# SCH_HomeAuto_2022-10-05.net
KiCad netlist of a schematic drawn in EasyEDA
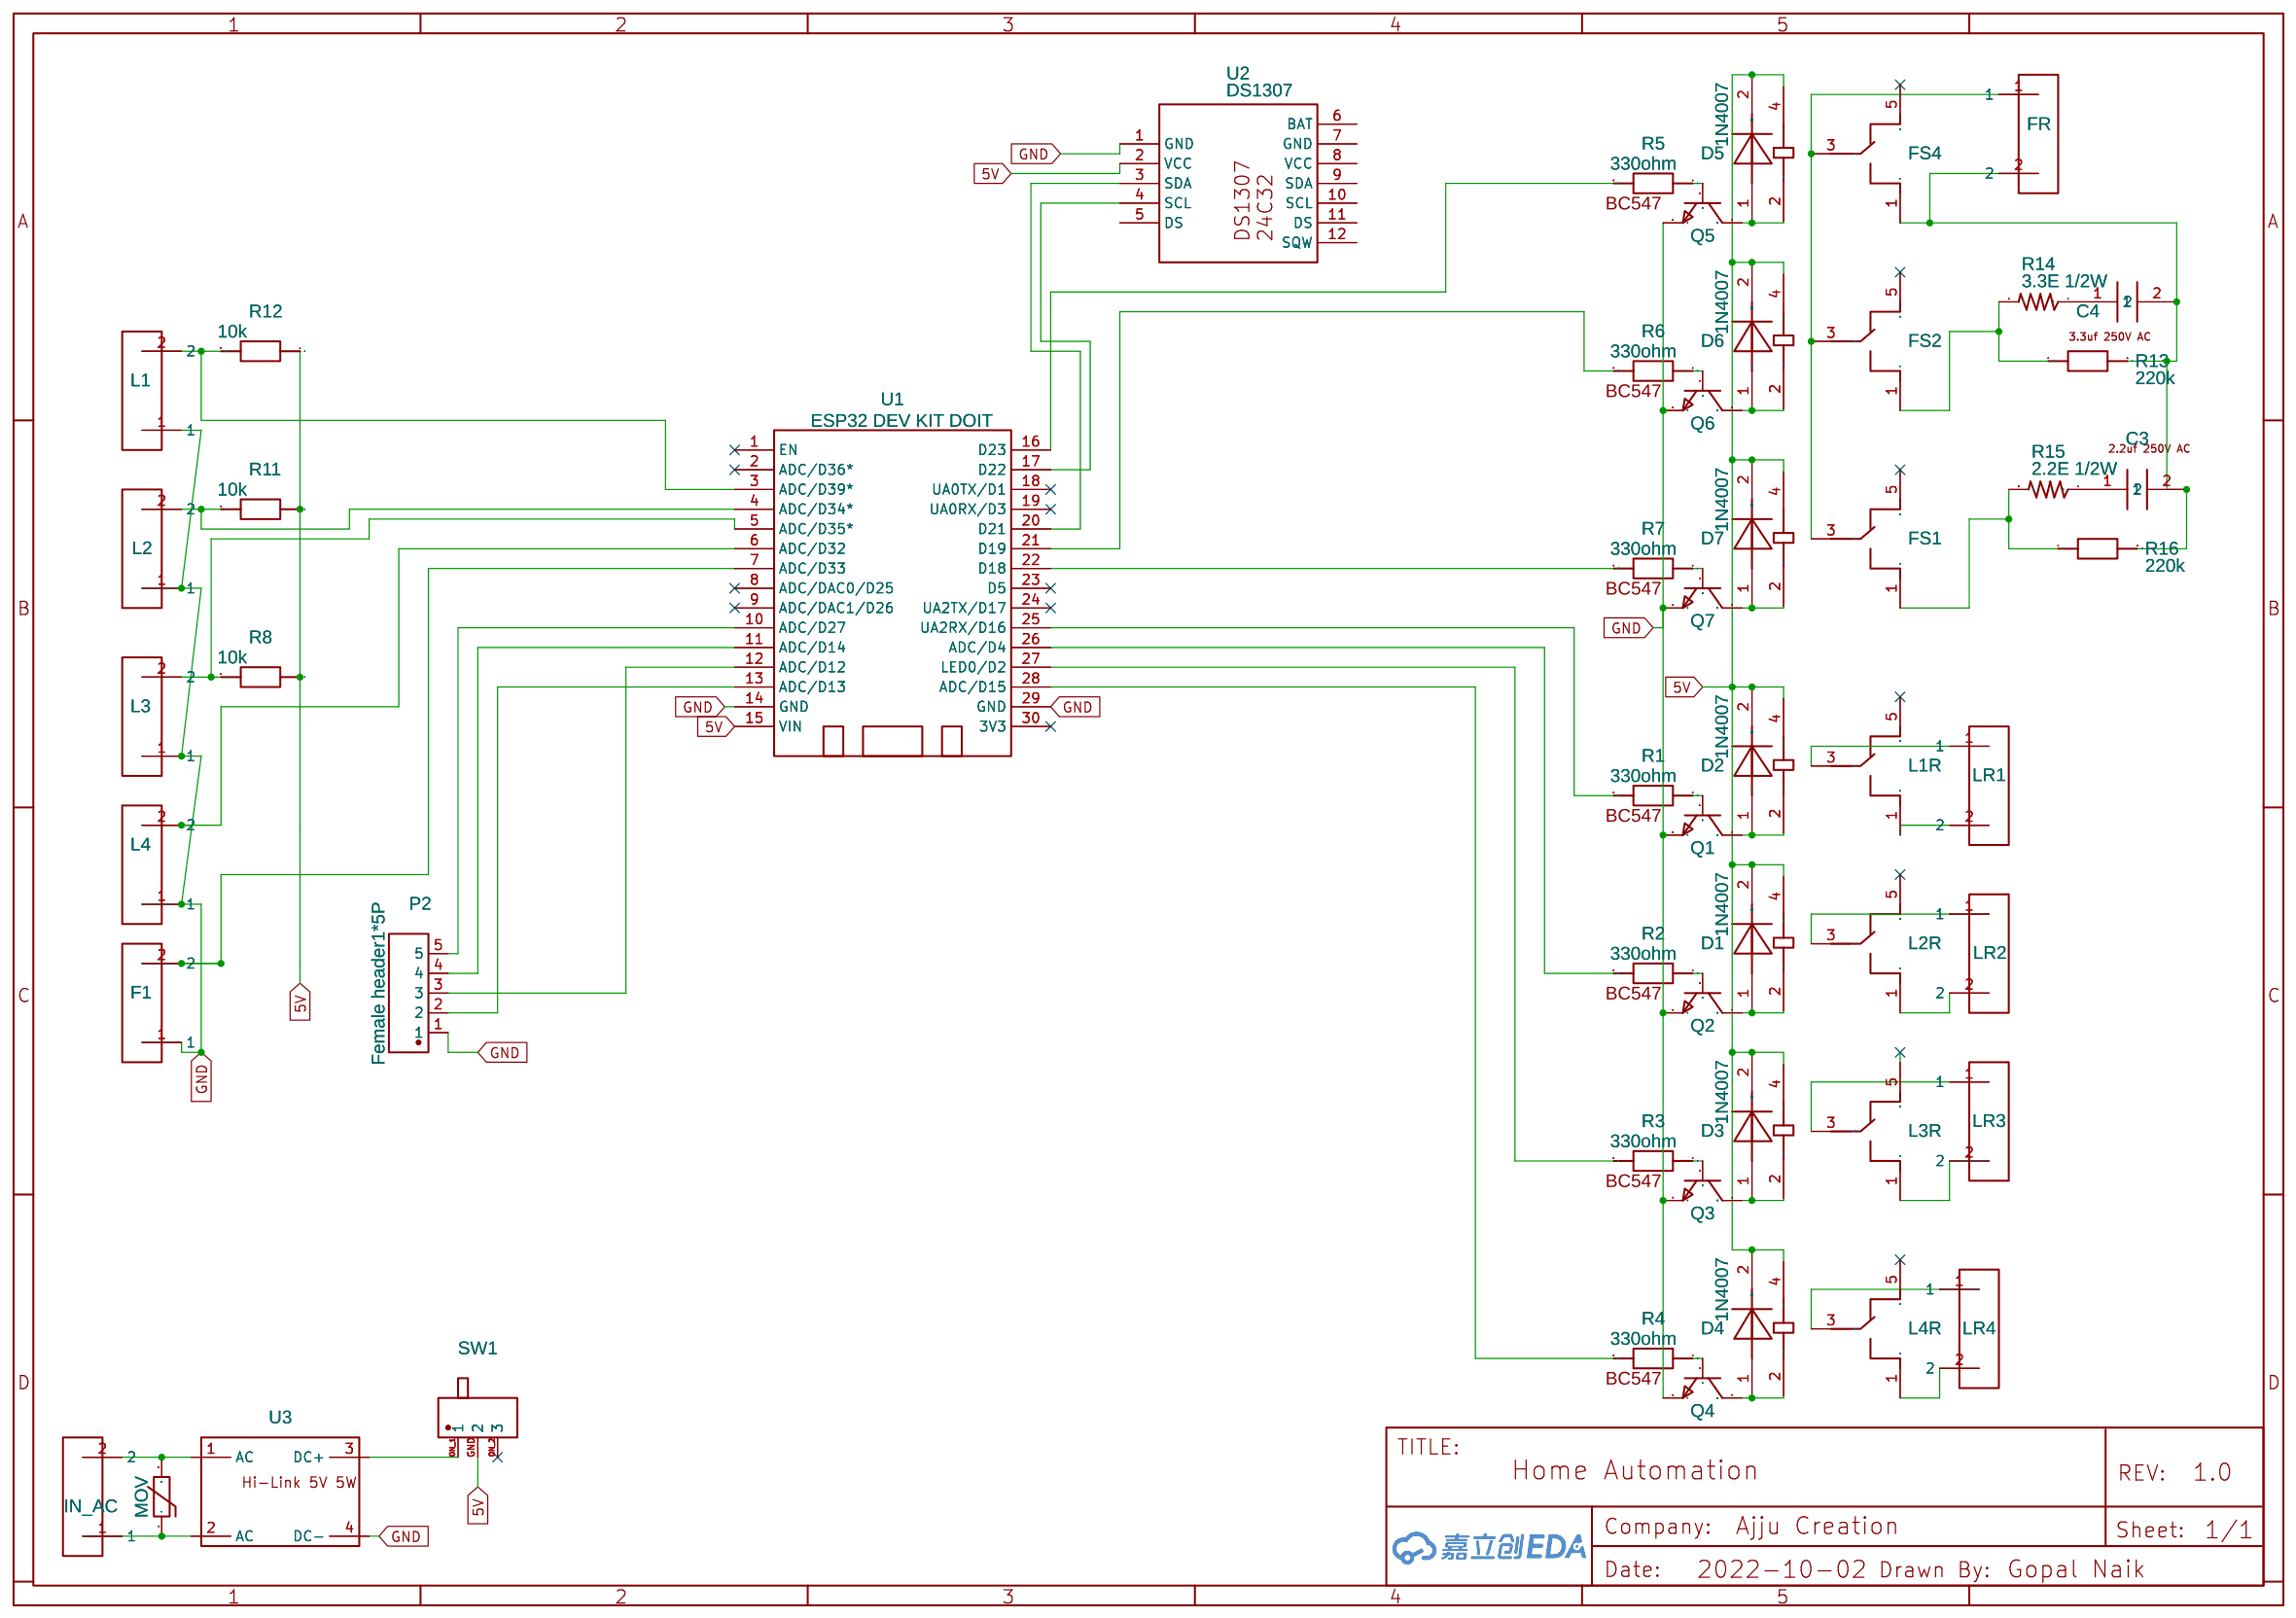
[diagram p0: schematic sheet]

(export (version "E")
  (design (tool "Eeschema 10.0.6"))
  (components
    (comp (ref "C3")
      (value "New_Symbol 2.2 uf 250v ac")
      (libsource (lib "") (part "New_Symbol 2.2 uf 250v ac"))
    )
    (comp (ref "C4")
      (value "New_Symbol 2.2 uf 250v ac")
      (libsource (lib "") (part "New_Symbol 2.2 uf 250v ac_1"))
    )
    (comp (ref "D1")
      (value "1N4007")
      (fields (field (name "BOM_Manufacturer Part") "DIODE") (field (name "BOM_Supplier Part") "undefined"))
      (libsource (lib "") (part "1N4007"))
    )
    (comp (ref "D2")
      (value "1N4007")
      (fields (field (name "BOM_Manufacturer Part") "DIODE") (field (name "BOM_Supplier Part") "undefined"))
      (libsource (lib "") (part "1N4007"))
    )
    (comp (ref "D3")
      (value "1N4007")
      (fields (field (name "BOM_Manufacturer Part") "DIODE") (field (name "BOM_Supplier Part") "undefined"))
      (libsource (lib "") (part "1N4007"))
    )
    (comp (ref "D4")
      (value "1N4007")
      (fields (field (name "BOM_Manufacturer Part") "DIODE") (field (name "BOM_Supplier Part") "undefined"))
      (libsource (lib "") (part "1N4007"))
    )
    (comp (ref "D5")
      (value "1N4007")
      (fields (field (name "BOM_Manufacturer Part") "DIODE") (field (name "BOM_Supplier Part") "undefined"))
      (libsource (lib "") (part "1N4007"))
    )
    (comp (ref "D6")
      (value "1N4007")
      (fields (field (name "BOM_Manufacturer Part") "DIODE") (field (name "BOM_Supplier Part") "undefined"))
      (libsource (lib "") (part "1N4007"))
    )
    (comp (ref "D7")
      (value "1N4007")
      (fields (field (name "BOM_Manufacturer Part") "DIODE") (field (name "BOM_Supplier Part") "undefined"))
      (libsource (lib "") (part "1N4007"))
    )
    (comp (ref "F1")
      (value "2 Pin Plug-In Screw Terminal Block 5.08mm pitch")
      (libsource (lib "") (part "2 Pin Plug-In Screw Terminal Block 5.08mm pitch_4"))
    )
    (comp (ref "FR")
      (value "2 Pin Plug-In Screw Terminal Block 5.08mm pitch")
      (libsource (lib "") (part "2 Pin Plug-In Screw Terminal Block 5.08mm pitch"))
    )
    (comp (ref "FS1")
      (value "RELAY-SPST")
      (fields
        (field (name "BOM_Manufacturer Part") "Relay-SPST")
        (field (name "BOM_Supplier Part") "C2941249")
      )
      (libsource (lib "") (part "RELAY-SPST"))
    )
    (comp (ref "FS2")
      (value "RELAY-SPST")
      (fields
        (field (name "BOM_Manufacturer Part") "Relay-SPST")
        (field (name "BOM_Supplier Part") "C2941249")
      )
      (libsource (lib "") (part "RELAY-SPST"))
    )
    (comp (ref "FS4")
      (value "RELAY-SPST")
      (fields
        (field (name "BOM_Manufacturer Part") "Relay-SPST")
        (field (name "BOM_Supplier Part") "C2941249")
      )
      (libsource (lib "") (part "RELAY-SPST"))
    )
    (comp (ref "IN_AC")
      (value "2 Pin Plug-In Screw Terminal Block 5.08mm pitch")
      (libsource (lib "") (part "2 Pin Plug-In Screw Terminal Block 5.08mm pitch_3"))
    )
    (comp (ref "L1")
      (value "2 Pin Plug-In Screw Terminal Block 5.08mm pitch")
      (libsource (lib "") (part "2 Pin Plug-In Screw Terminal Block 5.08mm pitch_1"))
    )
    (comp (ref "L1R")
      (value "RELAY-SPST")
      (fields
        (field (name "BOM_Manufacturer Part") "Relay-SPST")
        (field (name "BOM_Supplier Part") "C2941249")
      )
      (libsource (lib "") (part "RELAY-SPST_3"))
    )
    (comp (ref "L2")
      (value "2 Pin Plug-In Screw Terminal Block 5.08mm pitch")
      (libsource (lib "") (part "2 Pin Plug-In Screw Terminal Block 5.08mm pitch_1"))
    )
    (comp (ref "L2R")
      (value "RELAY-SPST")
      (fields
        (field (name "BOM_Manufacturer Part") "Relay-SPST")
        (field (name "BOM_Supplier Part") "C2941249")
      )
      (libsource (lib "") (part "RELAY-SPST_4"))
    )
    (comp (ref "L3")
      (value "2 Pin Plug-In Screw Terminal Block 5.08mm pitch")
      (libsource (lib "") (part "2 Pin Plug-In Screw Terminal Block 5.08mm pitch_1"))
    )
    (comp (ref "L3R")
      (value "RELAY-SPST")
      (fields
        (field (name "BOM_Manufacturer Part") "Relay-SPST")
        (field (name "BOM_Supplier Part") "C2941249")
      )
      (libsource (lib "") (part "RELAY-SPST_1"))
    )
    (comp (ref "L4")
      (value "2 Pin Plug-In Screw Terminal Block 5.08mm pitch")
      (libsource (lib "") (part "2 Pin Plug-In Screw Terminal Block 5.08mm pitch_1"))
    )
    (comp (ref "L4R")
      (value "RELAY-SPST")
      (fields
        (field (name "BOM_Manufacturer Part") "Relay-SPST")
        (field (name "BOM_Supplier Part") "C2941249")
      )
      (libsource (lib "") (part "RELAY-SPST_2"))
    )
    (comp (ref "LR1")
      (value "2 Pin Plug-In Screw Terminal Block 5.08mm pitch")
      (libsource (lib "") (part "2 Pin Plug-In Screw Terminal Block 5.08mm pitch_2"))
    )
    (comp (ref "LR2")
      (value "2 Pin Plug-In Screw Terminal Block 5.08mm pitch")
      (libsource (lib "") (part "2 Pin Plug-In Screw Terminal Block 5.08mm pitch_2"))
    )
    (comp (ref "LR3")
      (value "2 Pin Plug-In Screw Terminal Block 5.08mm pitch")
      (libsource (lib "") (part "2 Pin Plug-In Screw Terminal Block 5.08mm pitch_2"))
    )
    (comp (ref "LR4")
      (value "2 Pin Plug-In Screw Terminal Block 5.08mm pitch")
      (libsource (lib "") (part "2 Pin Plug-In Screw Terminal Block 5.08mm pitch_2"))
    )
    (comp (ref "P2")
      (value "Female header1*5P")
      (fields (field (name "BOM_Supplier Part") "C66508"))
      (libsource (lib "") (part "Female header1*5P"))
    )
    (comp (ref "Q1") (value "BC547") (libsource (lib "") (part "BC547")))
    (comp (ref "Q2") (value "BC547") (libsource (lib "") (part "BC547")))
    (comp (ref "Q3") (value "BC547") (libsource (lib "") (part "BC547")))
    (comp (ref "Q4") (value "BC547") (libsource (lib "") (part "BC547")))
    (comp (ref "Q5") (value "BC547") (libsource (lib "") (part "BC547")))
    (comp (ref "Q6") (value "BC547") (libsource (lib "") (part "BC547")))
    (comp (ref "Q7") (value "BC547") (libsource (lib "") (part "BC547")))
    (comp (ref "R1") (value "330ohm") (libsource (lib "") (part "330 OHM 0.25W 11MM")))
    (comp (ref "R2") (value "330ohm") (libsource (lib "") (part "330 OHM 0.25W 11MM")))
    (comp (ref "R3") (value "330ohm") (libsource (lib "") (part "330 OHM 0.25W 11MM")))
    (comp (ref "R4") (value "330ohm") (libsource (lib "") (part "330 OHM 0.25W 11MM")))
    (comp (ref "R5") (value "330ohm") (libsource (lib "") (part "330 OHM 0.25W 11MM")))
    (comp (ref "R6") (value "330ohm") (libsource (lib "") (part "330 OHM 0.25W 11MM")))
    (comp (ref "R7") (value "330ohm") (libsource (lib "") (part "330 OHM 0.25W 11MM")))
    (comp (ref "R8") (value "10k") (libsource (lib "") (part "330 OHM 0.25W 11MM")))
    (comp (ref "R11") (value "10k") (libsource (lib "") (part "330 OHM 0.25W 11MM")))
    (comp (ref "R12") (value "10k") (libsource (lib "") (part "330 OHM 0.25W 11MM")))
    (comp (ref "R13") (value "220k") (libsource (lib "") (part "330 OHM 0.25W 11MM_1")))
    (comp (ref "R14") (value "3.3E 1/2W") (libsource (lib "") (part "2.2E RESISTANCE 1/2W")))
    (comp (ref "R15") (value "2.2E 1/2W") (libsource (lib "") (part "2.2E RESISTANCE 1/2W")))
    (comp (ref "R16") (value "220k") (libsource (lib "") (part "330 OHM 0.25W 11MM_1")))
    (comp (ref "SW1")
      (value "3-Pin SPDT Slide Switch")
      (fields
        (field (name "BOM_Manufacturer Part") "5MS1S102BM1QES")
        (field (name "BOM_Supplier Part") "C496203")
      )
      (libsource (lib "") (part "3-Pin SPDT Slide Switch"))
    )
    (comp (ref "U1") (value "ESP32 DEV KIT DOIT") (libsource (lib "") (part "ESP32 DEV KIT DOIT")))
    (comp (ref "U2")
      (value "DS1307")
      (fields (field (name "BOM_Supplier Part") "undefined"))
      (libsource (lib "") (part "DS1307"))
    )
    (comp (ref "U3")
      (value "HLK-5M05 Hi-Link 5V 5W")
      (fields
        (field (name "BOM_Manufacturer Part") "HLK-5M05")
        (field (name "BOM_Supplier Part") "Hi-Link AC-DC Module 5V 1A - 5W")
      )
      (libsource (lib "") (part "HLK-5M05 Hi-Link 5V 5W"))
    )
    (comp (ref "VAR1")
      (value "MOV")
      (fields
        (field (name "BOM_Manufacturer Part") "MOV-14D781K")
        (field (name "BOM_Supplier Part") "652-MOV-14D781K")
      )
      (libsource (lib "") (part "VAR - MOV-14D781K"))
    )
  )
  (nets
    (net (code "1") (name "5V") (class "Default")
      (node (ref "D1") (pin "2") (pinfunction "Diode_IN4007_2") (pintype "unspecified"))
      (node (ref "D2") (pin "2") (pinfunction "Diode_IN4007_2") (pintype "unspecified"))
      (node (ref "D3") (pin "2") (pinfunction "Diode_IN4007_2") (pintype "unspecified"))
      (node (ref "D4") (pin "2") (pinfunction "Diode_IN4007_2") (pintype "unspecified"))
      (node (ref "D5") (pin "2") (pinfunction "Diode_IN4007_2") (pintype "unspecified"))
      (node (ref "D6") (pin "2") (pinfunction "Diode_IN4007_2") (pintype "unspecified"))
      (node (ref "D7") (pin "2") (pinfunction "Diode_IN4007_2") (pintype "unspecified"))
      (node (ref "FS1") (pin "4") (pinfunction "4_4") (pintype "unspecified"))
      (node (ref "FS2") (pin "4") (pinfunction "4_4") (pintype "unspecified"))
      (node (ref "FS4") (pin "4") (pinfunction "4_4") (pintype "unspecified"))
      (node (ref "L1R") (pin "4") (pinfunction "4_4") (pintype "unspecified"))
      (node (ref "L2R") (pin "4") (pinfunction "4_4") (pintype "unspecified"))
      (node (ref "L3R") (pin "4") (pinfunction "4_4") (pintype "unspecified"))
      (node (ref "L4R") (pin "4") (pinfunction "4_4") (pintype "unspecified"))
      (node (ref "R11") (pin "1") (pinfunction "1_1") (pintype "unspecified"))
      (node (ref "R12") (pin "1") (pinfunction "1_1") (pintype "unspecified"))
      (node (ref "R8") (pin "1") (pinfunction "1_1") (pintype "unspecified"))
      (node (ref "SW1") (pin "GND") (pinfunction "2_GND") (pintype "unspecified"))
      (node (ref "U1") (pin "15") (pinfunction "VIN_15") (pintype "input"))
      (node (ref "U2") (pin "2") (pinfunction "VCC_2") (pintype "unspecified"))
    )
    (net (code "2") (name "GND") (class "Default")
      (node (ref "F1") (pin "1") (pinfunction "1_1") (pintype "unspecified"))
      (node (ref "L1") (pin "1") (pinfunction "1_1") (pintype "unspecified"))
      (node (ref "L2") (pin "1") (pinfunction "1_1") (pintype "unspecified"))
      (node (ref "L3") (pin "1") (pinfunction "1_1") (pintype "unspecified"))
      (node (ref "L4") (pin "1") (pinfunction "1_1") (pintype "unspecified"))
      (node (ref "P2") (pin "1") (pinfunction "1_1") (pintype "unspecified"))
      (node (ref "Q1") (pin "3") (pinfunction "E_3") (pintype "unspecified"))
      (node (ref "Q2") (pin "3") (pinfunction "E_3") (pintype "unspecified"))
      (node (ref "Q3") (pin "3") (pinfunction "E_3") (pintype "unspecified"))
      (node (ref "Q4") (pin "3") (pinfunction "E_3") (pintype "unspecified"))
      (node (ref "Q5") (pin "3") (pinfunction "E_3") (pintype "unspecified"))
      (node (ref "Q6") (pin "3") (pinfunction "E_3") (pintype "unspecified"))
      (node (ref "Q7") (pin "3") (pinfunction "E_3") (pintype "unspecified"))
      (node (ref "U1") (pin "14") (pinfunction "GND_14") (pintype "bidirectional"))
      (node (ref "U1") (pin "29") (pinfunction "GND_29") (pintype "bidirectional"))
      (node (ref "U2") (pin "1") (pinfunction "GND_1") (pintype "unspecified"))
      (node (ref "U3") (pin "4") (pinfunction "DC-_4") (pintype "unspecified"))
    )
    (net (code "3") (name "Net-(C3-Pad1)") (class "Default")
      (node (ref "C3") (pin "1") (pinfunction "1_1") (pintype "unspecified"))
      (node (ref "R15") (pin "1") (pinfunction "1_1") (pintype "unspecified"))
    )
    (net (code "4") (name "Net-(C3-Pad2)") (class "Default")
      (node (ref "C3") (pin "2") (pinfunction "2_2") (pintype "unspecified"))
      (node (ref "C4") (pin "2") (pinfunction "2_2") (pintype "unspecified"))
      (node (ref "FR") (pin "2") (pinfunction "2_2") (pintype "unspecified"))
      (node (ref "FS4") (pin "1") (pinfunction "1_1") (pintype "unspecified"))
      (node (ref "R13") (pin "2") (pinfunction "2_2") (pintype "unspecified"))
      (node (ref "R16") (pin "2") (pinfunction "2_2") (pintype "unspecified"))
    )
    (net (code "5") (name "Net-(C4-Pad1)") (class "Default")
      (node (ref "C4") (pin "1") (pinfunction "1_1") (pintype "unspecified"))
      (node (ref "R14") (pin "1") (pinfunction "1_1") (pintype "unspecified"))
    )
    (net (code "6") (name "Net-(FR-Pad1)") (class "Default")
      (node (ref "FR") (pin "1") (pinfunction "1_1") (pintype "unspecified"))
      (node (ref "FS1") (pin "3") (pinfunction "3_3") (pintype "unspecified"))
      (node (ref "FS2") (pin "3") (pinfunction "3_3") (pintype "unspecified"))
      (node (ref "FS4") (pin "3") (pinfunction "3_3") (pintype "unspecified"))
    )
    (net (code "7") (name "Net-(FS1-Pad1)") (class "Default")
      (node (ref "FS1") (pin "1") (pinfunction "1_1") (pintype "unspecified"))
      (node (ref "R15") (pin "2") (pinfunction "2_2") (pintype "unspecified"))
      (node (ref "R16") (pin "1") (pinfunction "1_1") (pintype "unspecified"))
    )
    (net (code "8") (name "Net-(FS2-Pad1)") (class "Default")
      (node (ref "FS2") (pin "1") (pinfunction "1_1") (pintype "unspecified"))
      (node (ref "R13") (pin "1") (pinfunction "1_1") (pintype "unspecified"))
      (node (ref "R14") (pin "2") (pinfunction "2_2") (pintype "unspecified"))
    )
    (net (code "9") (name "Net-(IN_AC-Pad1)") (class "Default")
      (node (ref "IN_AC") (pin "1") (pinfunction "1_1") (pintype "unspecified"))
      (node (ref "U3") (pin "2") (pinfunction "AC_2") (pintype "unspecified"))
      (node (ref "VAR1") (pin "1") (pinfunction "1_1") (pintype "unspecified"))
    )
    (net (code "10") (name "Net-(IN_AC-Pad2)") (class "Default")
      (node (ref "IN_AC") (pin "2") (pinfunction "2_2") (pintype "unspecified"))
      (node (ref "U3") (pin "1") (pinfunction "AC_1") (pintype "unspecified"))
      (node (ref "VAR1") (pin "2") (pinfunction "2_2") (pintype "unspecified"))
    )
    (net (code "11") (name "Net-(L1R-Pad1)") (class "Default")
      (node (ref "L1R") (pin "1") (pinfunction "1_1") (pintype "unspecified"))
      (node (ref "LR1") (pin "2") (pinfunction "2_2") (pintype "unspecified"))
    )
    (net (code "12") (name "Net-(L1R-Pad3)") (class "Default")
      (node (ref "L1R") (pin "3") (pinfunction "3_3") (pintype "unspecified"))
      (node (ref "LR1") (pin "1") (pinfunction "1_1") (pintype "unspecified"))
    )
    (net (code "13") (name "Net-(L2R-Pad1)") (class "Default")
      (node (ref "L2R") (pin "1") (pinfunction "1_1") (pintype "unspecified"))
      (node (ref "LR2") (pin "2") (pinfunction "2_2") (pintype "unspecified"))
    )
    (net (code "14") (name "Net-(L2R-Pad3)") (class "Default")
      (node (ref "L2R") (pin "3") (pinfunction "3_3") (pintype "unspecified"))
      (node (ref "LR2") (pin "1") (pinfunction "1_1") (pintype "unspecified"))
    )
    (net (code "15") (name "Net-(L3R-Pad1)") (class "Default")
      (node (ref "L3R") (pin "1") (pinfunction "1_1") (pintype "unspecified"))
      (node (ref "LR3") (pin "2") (pinfunction "2_2") (pintype "unspecified"))
    )
    (net (code "16") (name "Net-(L3R-Pad3)") (class "Default")
      (node (ref "L3R") (pin "3") (pinfunction "3_3") (pintype "unspecified"))
      (node (ref "LR3") (pin "1") (pinfunction "1_1") (pintype "unspecified"))
    )
    (net (code "17") (name "Net-(L4R-Pad1)") (class "Default")
      (node (ref "L4R") (pin "1") (pinfunction "1_1") (pintype "unspecified"))
      (node (ref "LR4") (pin "2") (pinfunction "2_2") (pintype "unspecified"))
    )
    (net (code "18") (name "Net-(L4R-Pad3)") (class "Default")
      (node (ref "L4R") (pin "3") (pinfunction "3_3") (pintype "unspecified"))
      (node (ref "LR4") (pin "1") (pinfunction "1_1") (pintype "unspecified"))
    )
    (net (code "19") (name "Net-(Q1-B)") (class "Default")
      (node (ref "Q1") (pin "2") (pinfunction "B_2") (pintype "unspecified"))
      (node (ref "R1") (pin "1") (pinfunction "1_1") (pintype "unspecified"))
    )
    (net (code "20") (name "Net-(Q1-C)") (class "Default")
      (node (ref "D2") (pin "1") (pinfunction "1_1") (pintype "unspecified"))
      (node (ref "L1R") (pin "2") (pinfunction "2_2") (pintype "unspecified"))
      (node (ref "Q1") (pin "1") (pinfunction "C_1") (pintype "unspecified"))
    )
    (net (code "21") (name "Net-(Q2-B)") (class "Default")
      (node (ref "Q2") (pin "2") (pinfunction "B_2") (pintype "unspecified"))
      (node (ref "R2") (pin "1") (pinfunction "1_1") (pintype "unspecified"))
    )
    (net (code "22") (name "Net-(Q2-C)") (class "Default")
      (node (ref "D1") (pin "1") (pinfunction "1_1") (pintype "unspecified"))
      (node (ref "L2R") (pin "2") (pinfunction "2_2") (pintype "unspecified"))
      (node (ref "Q2") (pin "1") (pinfunction "C_1") (pintype "unspecified"))
    )
    (net (code "23") (name "Net-(Q3-B)") (class "Default")
      (node (ref "Q3") (pin "2") (pinfunction "B_2") (pintype "unspecified"))
      (node (ref "R3") (pin "1") (pinfunction "1_1") (pintype "unspecified"))
    )
    (net (code "24") (name "Net-(Q3-C)") (class "Default")
      (node (ref "D3") (pin "1") (pinfunction "1_1") (pintype "unspecified"))
      (node (ref "L3R") (pin "2") (pinfunction "2_2") (pintype "unspecified"))
      (node (ref "Q3") (pin "1") (pinfunction "C_1") (pintype "unspecified"))
    )
    (net (code "25") (name "Net-(Q4-B)") (class "Default")
      (node (ref "Q4") (pin "2") (pinfunction "B_2") (pintype "unspecified"))
      (node (ref "R4") (pin "1") (pinfunction "1_1") (pintype "unspecified"))
    )
    (net (code "26") (name "Net-(Q4-C)") (class "Default")
      (node (ref "D4") (pin "1") (pinfunction "1_1") (pintype "unspecified"))
      (node (ref "L4R") (pin "2") (pinfunction "2_2") (pintype "unspecified"))
      (node (ref "Q4") (pin "1") (pinfunction "C_1") (pintype "unspecified"))
    )
    (net (code "27") (name "Net-(Q5-B)") (class "Default")
      (node (ref "Q5") (pin "2") (pinfunction "B_2") (pintype "unspecified"))
      (node (ref "R5") (pin "1") (pinfunction "1_1") (pintype "unspecified"))
    )
    (net (code "28") (name "Net-(Q5-C)") (class "Default")
      (node (ref "D5") (pin "1") (pinfunction "1_1") (pintype "unspecified"))
      (node (ref "FS4") (pin "2") (pinfunction "2_2") (pintype "unspecified"))
      (node (ref "Q5") (pin "1") (pinfunction "C_1") (pintype "unspecified"))
    )
    (net (code "29") (name "Net-(Q6-B)") (class "Default")
      (node (ref "Q6") (pin "2") (pinfunction "B_2") (pintype "unspecified"))
      (node (ref "R6") (pin "1") (pinfunction "1_1") (pintype "unspecified"))
    )
    (net (code "30") (name "Net-(Q6-C)") (class "Default")
      (node (ref "D6") (pin "1") (pinfunction "1_1") (pintype "unspecified"))
      (node (ref "FS2") (pin "2") (pinfunction "2_2") (pintype "unspecified"))
      (node (ref "Q6") (pin "1") (pinfunction "C_1") (pintype "unspecified"))
    )
    (net (code "31") (name "Net-(Q7-B)") (class "Default")
      (node (ref "Q7") (pin "2") (pinfunction "B_2") (pintype "unspecified"))
      (node (ref "R7") (pin "1") (pinfunction "1_1") (pintype "unspecified"))
    )
    (net (code "32") (name "Net-(Q7-C)") (class "Default")
      (node (ref "D7") (pin "1") (pinfunction "1_1") (pintype "unspecified"))
      (node (ref "FS1") (pin "2") (pinfunction "2_2") (pintype "unspecified"))
      (node (ref "Q7") (pin "1") (pinfunction "C_1") (pintype "unspecified"))
    )
    (net (code "33") (name "Net-(SW1-1)") (class "Default")
      (node (ref "SW1") (pin "ON_1") (pinfunction "1_ON_1") (pintype "unspecified"))
      (node (ref "U3") (pin "3") (pinfunction "DC+_3") (pintype "unspecified"))
    )
    (net (code "34") (name "Net-(U1-ADC{slash}D4)") (class "Default")
      (node (ref "R2") (pin "2") (pinfunction "2_2") (pintype "unspecified"))
      (node (ref "U1") (pin "26") (pinfunction "ADC/D4_26") (pintype "bidirectional"))
    )
    (net (code "35") (name "Net-(U1-ADC{slash}D12)") (class "Default")
      (node (ref "P2") (pin "3") (pinfunction "3_3") (pintype "unspecified"))
      (node (ref "U1") (pin "12") (pinfunction "ADC/D12_12") (pintype "bidirectional"))
    )
    (net (code "36") (name "Net-(U1-ADC{slash}D13)") (class "Default")
      (node (ref "P2") (pin "2") (pinfunction "2_2") (pintype "unspecified"))
      (node (ref "U1") (pin "13") (pinfunction "ADC/D13_13") (pintype "bidirectional"))
    )
    (net (code "37") (name "Net-(U1-ADC{slash}D14)") (class "Default")
      (node (ref "P2") (pin "4") (pinfunction "4_4") (pintype "unspecified"))
      (node (ref "U1") (pin "11") (pinfunction "ADC/D14_11") (pintype "bidirectional"))
    )
    (net (code "38") (name "Net-(U1-ADC{slash}D15)") (class "Default")
      (node (ref "R4") (pin "2") (pinfunction "2_2") (pintype "unspecified"))
      (node (ref "U1") (pin "28") (pinfunction "ADC/D15_28") (pintype "bidirectional"))
    )
    (net (code "39") (name "Net-(U1-ADC{slash}D27)") (class "Default")
      (node (ref "P2") (pin "5") (pinfunction "5_5") (pintype "unspecified"))
      (node (ref "U1") (pin "10") (pinfunction "ADC/D27_10") (pintype "bidirectional"))
    )
    (net (code "40") (name "Net-(U1-ADC{slash}D32)") (class "Default")
      (node (ref "L4") (pin "2") (pinfunction "2_2") (pintype "unspecified"))
      (node (ref "U1") (pin "6") (pinfunction "ADC/D32_6") (pintype "bidirectional"))
    )
    (net (code "41") (name "Net-(U1-ADC{slash}D33)") (class "Default")
      (node (ref "F1") (pin "2") (pinfunction "2_2") (pintype "unspecified"))
      (node (ref "U1") (pin "7") (pinfunction "ADC/D33_7") (pintype "bidirectional"))
    )
    (net (code "42") (name "Net-(U1-ADC{slash}D34*)") (class "Default")
      (node (ref "L2") (pin "2") (pinfunction "2_2") (pintype "unspecified"))
      (node (ref "R11") (pin "2") (pinfunction "2_2") (pintype "unspecified"))
      (node (ref "U1") (pin "4") (pinfunction "ADC/D34*_4") (pintype "input"))
    )
    (net (code "43") (name "Net-(U1-ADC{slash}D35*)") (class "Default")
      (node (ref "L3") (pin "2") (pinfunction "2_2") (pintype "unspecified"))
      (node (ref "R8") (pin "2") (pinfunction "2_2") (pintype "unspecified"))
      (node (ref "U1") (pin "5") (pinfunction "ADC/D35*_5") (pintype "input"))
    )
    (net (code "44") (name "Net-(U1-ADC{slash}D39*)") (class "Default")
      (node (ref "L1") (pin "2") (pinfunction "2_2") (pintype "unspecified"))
      (node (ref "R12") (pin "2") (pinfunction "2_2") (pintype "unspecified"))
      (node (ref "U1") (pin "3") (pinfunction "ADC/D39*_3") (pintype "input"))
    )
    (net (code "45") (name "Net-(U1-D18)") (class "Default")
      (node (ref "R7") (pin "2") (pinfunction "2_2") (pintype "unspecified"))
      (node (ref "U1") (pin "22") (pinfunction "D18_22") (pintype "bidirectional"))
    )
    (net (code "46") (name "Net-(U1-D19)") (class "Default")
      (node (ref "R6") (pin "2") (pinfunction "2_2") (pintype "unspecified"))
      (node (ref "U1") (pin "21") (pinfunction "D19_21") (pintype "bidirectional"))
    )
    (net (code "47") (name "Net-(U1-D21)") (class "Default")
      (node (ref "U1") (pin "20") (pinfunction "D21_20") (pintype "bidirectional"))
      (node (ref "U2") (pin "3") (pinfunction "SDA_3") (pintype "unspecified"))
    )
    (net (code "48") (name "Net-(U1-D22)") (class "Default")
      (node (ref "U1") (pin "17") (pinfunction "D22_17") (pintype "bidirectional"))
      (node (ref "U2") (pin "4") (pinfunction "SCL_4") (pintype "unspecified"))
    )
    (net (code "49") (name "Net-(U1-D23)") (class "Default")
      (node (ref "R5") (pin "2") (pinfunction "2_2") (pintype "unspecified"))
      (node (ref "U1") (pin "16") (pinfunction "D23_16") (pintype "bidirectional"))
    )
    (net (code "50") (name "Net-(U1-LED0{slash}D2)") (class "Default")
      (node (ref "R3") (pin "2") (pinfunction "2_2") (pintype "unspecified"))
      (node (ref "U1") (pin "27") (pinfunction "LED0/D2_27") (pintype "bidirectional"))
    )
    (net (code "51") (name "Net-(U1-UA2RX{slash}D16)") (class "Default")
      (node (ref "R1") (pin "2") (pinfunction "2_2") (pintype "unspecified"))
      (node (ref "U1") (pin "25") (pinfunction "UA2RX/D16_25") (pintype "bidirectional"))
    )
    (net (code "52") (name "unconnected-(FS1-Pad5)") (class "Default")
      (node (ref "FS1") (pin "5") (pinfunction "5_5") (pintype "unspecified+no_connect"))
    )
    (net (code "53") (name "unconnected-(FS2-Pad5)") (class "Default")
      (node (ref "FS2") (pin "5") (pinfunction "5_5") (pintype "unspecified+no_connect"))
    )
    (net (code "54") (name "unconnected-(FS4-Pad5)") (class "Default")
      (node (ref "FS4") (pin "5") (pinfunction "5_5") (pintype "unspecified+no_connect"))
    )
    (net (code "55") (name "unconnected-(L1R-Pad5)") (class "Default")
      (node (ref "L1R") (pin "5") (pinfunction "5_5") (pintype "unspecified+no_connect"))
    )
    (net (code "56") (name "unconnected-(L2R-Pad5)") (class "Default")
      (node (ref "L2R") (pin "5") (pinfunction "5_5") (pintype "unspecified+no_connect"))
    )
    (net (code "57") (name "unconnected-(L3R-Pad5)") (class "Default")
      (node (ref "L3R") (pin "5") (pinfunction "5_5") (pintype "unspecified+no_connect"))
    )
    (net (code "58") (name "unconnected-(L4R-Pad5)") (class "Default")
      (node (ref "L4R") (pin "5") (pinfunction "5_5") (pintype "unspecified+no_connect"))
    )
    (net (code "59") (name "unconnected-(SW1-3-PadON_2)") (class "Default")
      (node (ref "SW1") (pin "ON_2") (pinfunction "3_ON_2") (pintype "unspecified+no_connect"))
    )
    (net (code "60") (name "unconnected-(U1-3V3-Pad30)") (class "Default")
      (node (ref "U1") (pin "30") (pinfunction "3V3_30") (pintype "bidirectional+no_connect"))
    )
    (net (code "61") (name "unconnected-(U1-ADC{slash}D36*-Pad2)") (class "Default")
      (node (ref "U1") (pin "2") (pinfunction "ADC/D36*_2") (pintype "input+no_connect"))
    )
    (net (code "62") (name "unconnected-(U1-ADC{slash}DAC0{slash}D25-Pad8)") (class "Default")
      (node (ref "U1") (pin "8") (pinfunction "ADC/DAC0/D25_8") (pintype "bidirectional+no_connect"))
    )
    (net (code "63") (name "unconnected-(U1-ADC{slash}DAC1{slash}D26-Pad9)") (class "Default")
      (node (ref "U1") (pin "9") (pinfunction "ADC/DAC1/D26_9") (pintype "bidirectional+no_connect"))
    )
    (net (code "64") (name "unconnected-(U1-D5-Pad23)") (class "Default")
      (node (ref "U1") (pin "23") (pinfunction "D5_23") (pintype "bidirectional+no_connect"))
    )
    (net (code "65") (name "unconnected-(U1-EN-Pad1)") (class "Default")
      (node (ref "U1") (pin "1") (pinfunction "EN_1") (pintype "bidirectional+no_connect"))
    )
    (net (code "66") (name "unconnected-(U1-UA0RX{slash}D3-Pad19)") (class "Default")
      (node (ref "U1") (pin "19") (pinfunction "UA0RX/D3_19") (pintype "bidirectional+no_connect"))
    )
    (net (code "67") (name "unconnected-(U1-UA0TX{slash}D1-Pad18)") (class "Default")
      (node (ref "U1") (pin "18") (pinfunction "UA0TX/D1_18") (pintype "bidirectional+no_connect"))
    )
    (net (code "68") (name "unconnected-(U1-UA2TX{slash}D17-Pad24)") (class "Default")
      (node (ref "U1") (pin "24") (pinfunction "UA2TX/D17_24") (pintype "bidirectional+no_connect"))
    )
    (net (code "69") (name "unconnected-(U2-BAT-Pad6)") (class "Default")
      (node (ref "U2") (pin "6") (pinfunction "BAT_6") (pintype "unspecified"))
    )
    (net (code "70") (name "unconnected-(U2-DS-Pad5)") (class "Default")
      (node (ref "U2") (pin "5") (pinfunction "DS_5") (pintype "unspecified"))
    )
    (net (code "71") (name "unconnected-(U2-DS-Pad11)") (class "Default")
      (node (ref "U2") (pin "11") (pinfunction "DS_11") (pintype "unspecified"))
    )
    (net (code "72") (name "unconnected-(U2-GND-Pad7)") (class "Default")
      (node (ref "U2") (pin "7") (pinfunction "GND_7") (pintype "unspecified"))
    )
    (net (code "73") (name "unconnected-(U2-SCL-Pad10)") (class "Default")
      (node (ref "U2") (pin "10") (pinfunction "SCL_10") (pintype "unspecified"))
    )
    (net (code "74") (name "unconnected-(U2-SDA-Pad9)") (class "Default")
      (node (ref "U2") (pin "9") (pinfunction "SDA_9") (pintype "unspecified"))
    )
    (net (code "75") (name "unconnected-(U2-SQW-Pad12)") (class "Default")
      (node (ref "U2") (pin "12") (pinfunction "SQW_12") (pintype "unspecified"))
    )
    (net (code "76") (name "unconnected-(U2-VCC-Pad8)") (class "Default")
      (node (ref "U2") (pin "8") (pinfunction "VCC_8") (pintype "unspecified"))
    )
  )
)
